# Control_Board.net
KiCad netlist of a schematic drawn in EAGLE
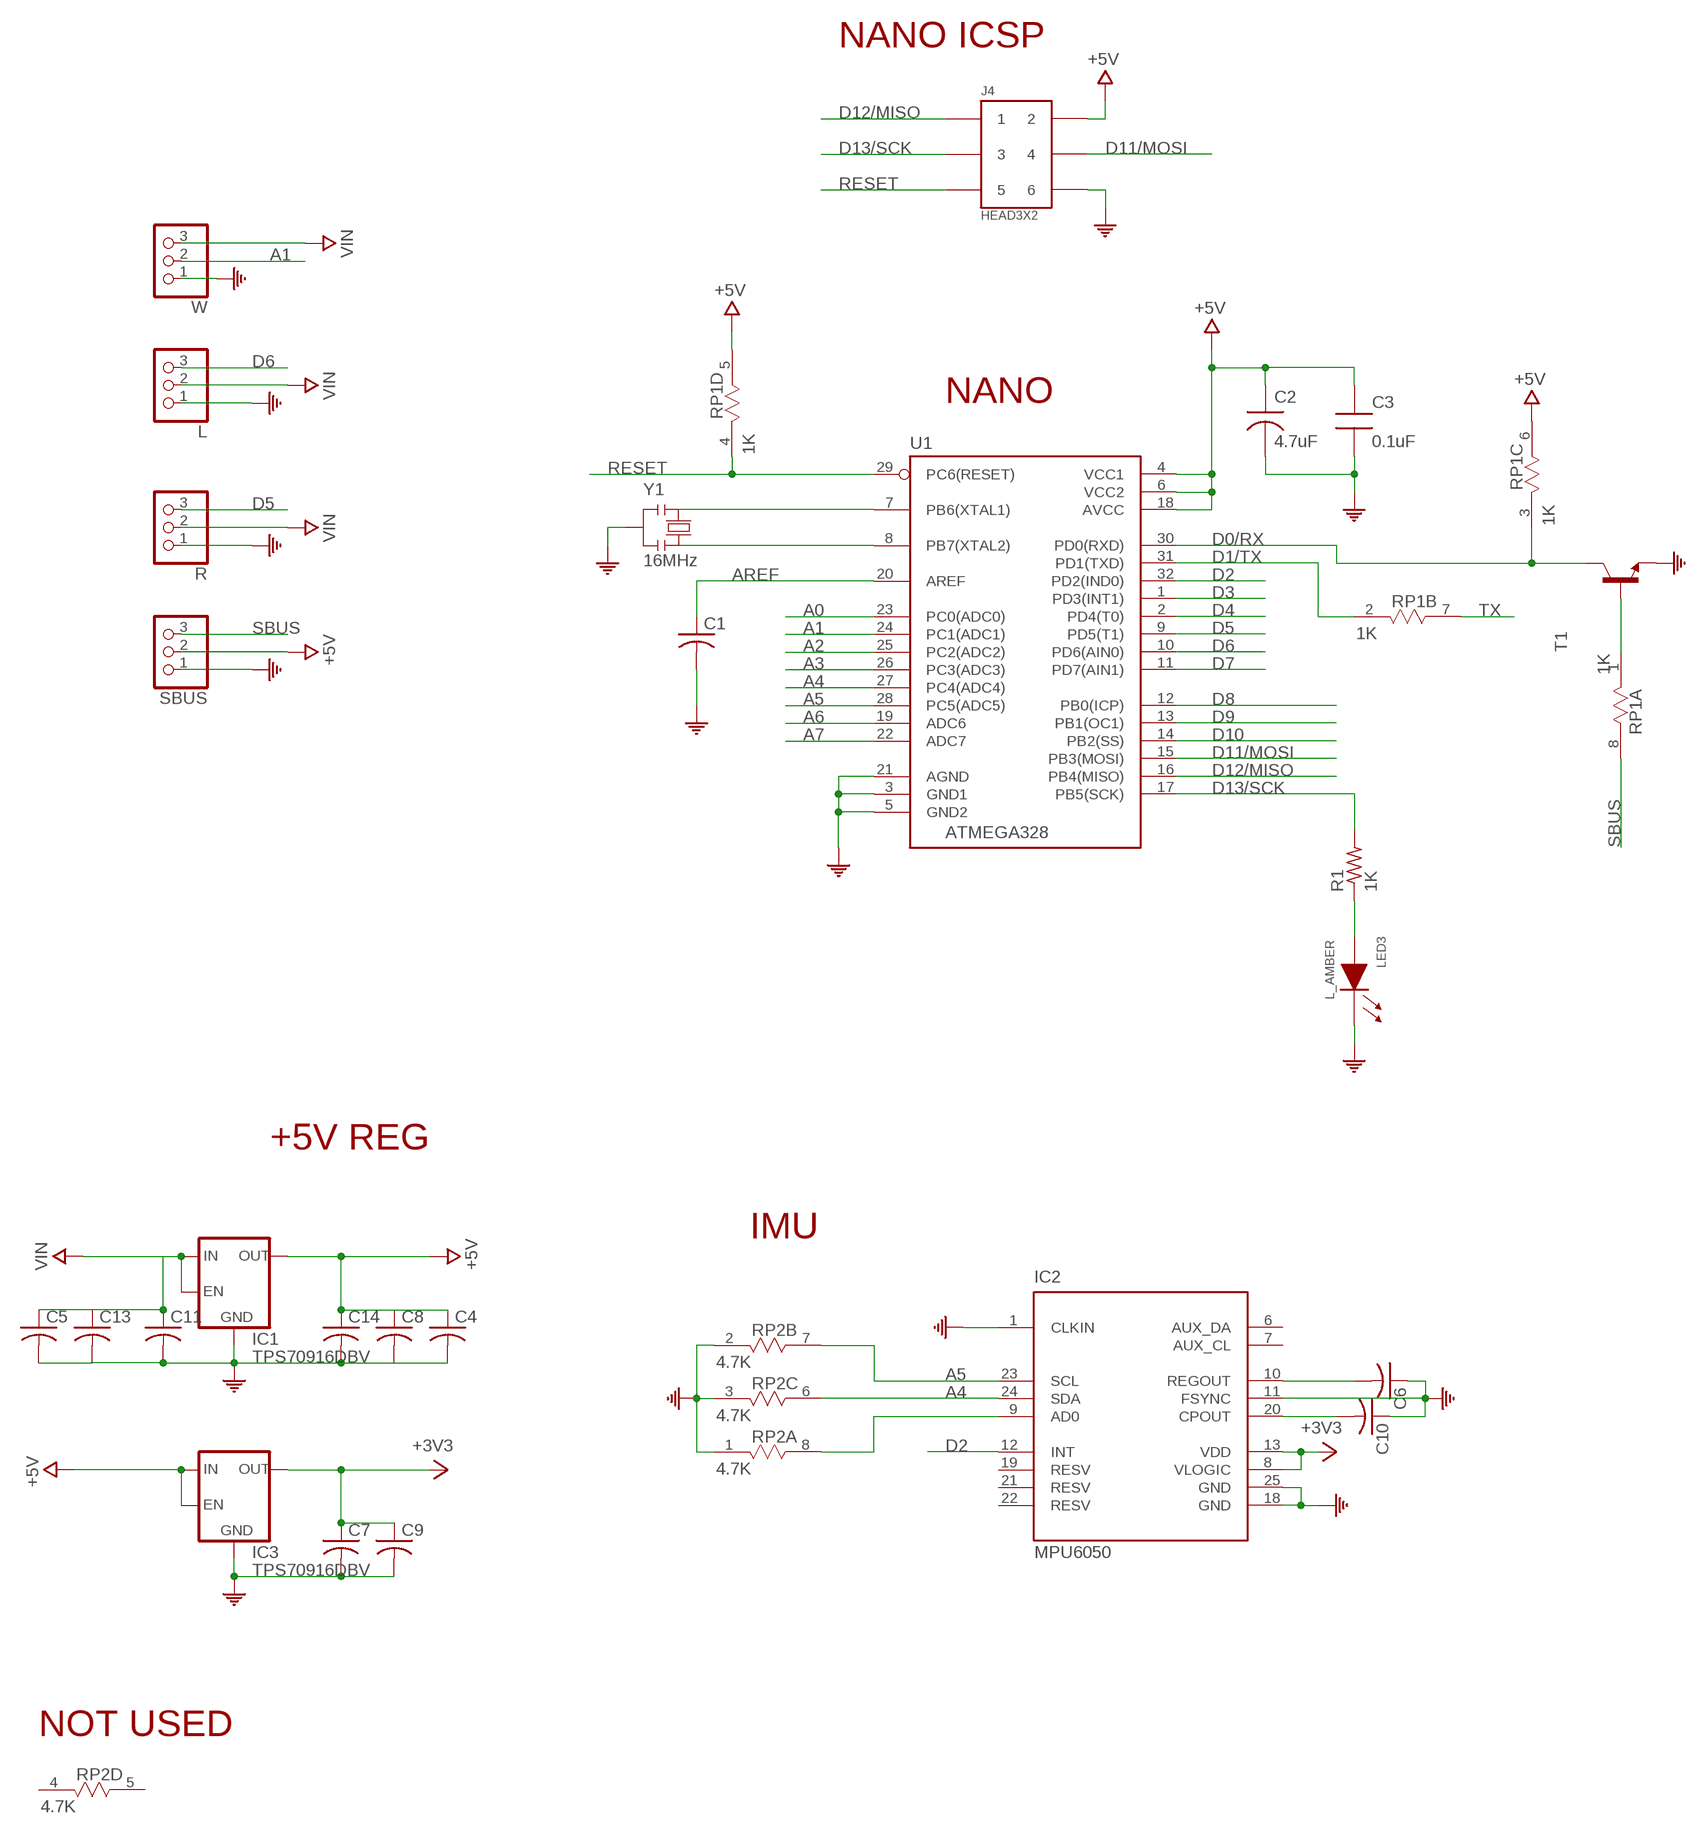
[diagram p0: schematic, sheet 1]

(export (version "E")
  (design (tool "Eeschema 10.0.6"))
  (components
    (comp (ref "C1")
      (value "C-USC0603")
      (footprint "eagle-import:C0603")
      (libsource (lib "eagle-import") (part "C-USC0603"))
    )
    (comp (ref "C2")
      (value "4.7uF")
      (footprint "eagle-import:TAN-A")
      (libsource (lib "eagle-import") (part "CAP-TANA-P"))
    )
    (comp (ref "C3")
      (value "0.1uF")
      (footprint "eagle-import:CAP0805-NP")
      (libsource (lib "eagle-import") (part "CAP0805-NP"))
    )
    (comp (ref "C4")
      (value "C-USC0603")
      (footprint "eagle-import:C0603")
      (libsource (lib "eagle-import") (part "C-USC0603"))
    )
    (comp (ref "C5")
      (value "C-USC0603")
      (footprint "eagle-import:C0603")
      (libsource (lib "eagle-import") (part "C-USC0603"))
    )
    (comp (ref "C6")
      (value "C-USC0603")
      (footprint "eagle-import:C0603")
      (libsource (lib "eagle-import") (part "C-USC0603"))
    )
    (comp (ref "C7")
      (value "C-USC0603")
      (footprint "eagle-import:C0603")
      (libsource (lib "eagle-import") (part "C-USC0603"))
    )
    (comp (ref "C8")
      (value "C-USC0603")
      (footprint "eagle-import:C0603")
      (libsource (lib "eagle-import") (part "C-USC0603"))
    )
    (comp (ref "C9")
      (value "C-USC0603")
      (footprint "eagle-import:C0603")
      (libsource (lib "eagle-import") (part "C-USC0603"))
    )
    (comp (ref "C10")
      (value "C-USC0603")
      (footprint "eagle-import:C0603")
      (libsource (lib "eagle-import") (part "C-USC0603"))
    )
    (comp (ref "C11")
      (value "C-USC0603")
      (footprint "eagle-import:C0603")
      (libsource (lib "eagle-import") (part "C-USC0603"))
    )
    (comp (ref "C13")
      (value "C-USC0603")
      (footprint "eagle-import:C0603")
      (libsource (lib "eagle-import") (part "C-USC0603"))
    )
    (comp (ref "C14")
      (value "C-USC0603")
      (footprint "eagle-import:C0603")
      (libsource (lib "eagle-import") (part "C-USC0603"))
    )
    (comp (ref "IC1")
      (value "TPS70916DBV")
      (footprint "eagle-import:SOT23-5")
      (fields (field (name "MF") "Texas Instruments") (field (name "MPN") "TPS70916DBVT"))
      (libsource (lib "eagle-import") (part "TPS709DBV16"))
    )
    (comp (ref "IC2")
      (value "MPU6050")
      (footprint "eagle-import:QFN50P400X400X95-25T265X275N")
      (libsource (lib "eagle-import") (part "MPU6050"))
    )
    (comp (ref "IC3")
      (value "TPS70916DBV")
      (footprint "eagle-import:SOT23-5")
      (fields (field (name "MF") "Texas Instruments") (field (name "MPN") "TPS70916DBVT"))
      (libsource (lib "eagle-import") (part "TPS709DBV16"))
    )
    (comp (ref "J4")
      (value "HEAD3X2")
      (footprint "eagle-import:HEAD3X2")
      (libsource (lib "eagle-import") (part "HEAD3X2"))
    )
    (comp (ref "L")
      (value "PINHD-1X3")
      (footprint "eagle-import:1X03")
      (libsource (lib "eagle-import") (part "PINHD-1X3"))
    )
    (comp (ref "LED3")
      (value "L_AMBER")
      (footprint "eagle-import:LED0805")
      (libsource (lib "eagle-import") (part "LED0805"))
    )
    (comp (ref "R")
      (value "PINHD-1X3")
      (footprint "eagle-import:1X03")
      (libsource (lib "eagle-import") (part "PINHD-1X3"))
    )
    (comp (ref "R1")
      (value "1K")
      (footprint "eagle-import:R0603")
      (libsource (lib "eagle-import") (part "R-US_R0603"))
    )
    (comp (ref "RP1")
      (value "1K")
      (footprint "eagle-import:RES4NT")
      (libsource (lib "eagle-import") (part "RES4NT"))
    )
    (comp (ref "RP2")
      (value "4.7K")
      (footprint "eagle-import:RES4NT")
      (libsource (lib "eagle-import") (part "RES4NT"))
    )
    (comp (ref "SBUS")
      (value "PINHD-1X3")
      (footprint "eagle-import:1X03")
      (libsource (lib "eagle-import") (part "PINHD-1X3"))
    )
    (comp (ref "T1")
      (value "MMBT3904LT1-NPN-SOT23-BEC")
      (footprint "eagle-import:SOT23-BEC")
      (libsource (lib "eagle-import") (part "-NPN-SOT23-BECMMBT3904LT1"))
    )
    (comp (ref "U1")
      (value "ATMEGA328")
      (footprint "eagle-import:QFP032")
      (libsource (lib "eagle-import") (part "ATMEGA168-20AU"))
    )
    (comp (ref "W")
      (value "PINHD-1X3")
      (footprint "eagle-import:1X03")
      (libsource (lib "eagle-import") (part "PINHD-1X3"))
    )
    (comp (ref "Y1")
      (value "16MHz")
      (footprint "eagle-import:RESONATOR")
      (libsource (lib "eagle-import") (part "RESONATORMU"))
    )
  )
  (nets
    (net (code "1") (name "+3V3") (class "Default")
      (node (ref "C7") (pin "1") (pinfunction "1_1") (pintype "passive"))
      (node (ref "C9") (pin "1") (pinfunction "1_1") (pintype "passive"))
      (node (ref "IC2") (pin "13") (pinfunction "VDD_13") (pintype "power_in"))
      (node (ref "IC2") (pin "8") (pinfunction "VLOGIC_8") (pintype "power_in"))
      (node (ref "IC3") (pin "5") (pinfunction "OUT_5") (pintype "passive"))
    )
    (net (code "2") (name "+5V") (class "Default")
      (node (ref "C14") (pin "1") (pinfunction "1_1") (pintype "passive"))
      (node (ref "C2") (pin "1") (pinfunction "1_1") (pintype "passive"))
      (node (ref "C3") (pin "1") (pinfunction "1_1") (pintype "passive"))
      (node (ref "C4") (pin "1") (pinfunction "1_1") (pintype "passive"))
      (node (ref "C8") (pin "1") (pinfunction "1_1") (pintype "passive"))
      (node (ref "IC1") (pin "5") (pinfunction "OUT_5") (pintype "passive"))
      (node (ref "IC3") (pin "1") (pinfunction "IN_1") (pintype "input"))
      (node (ref "IC3") (pin "3") (pinfunction "EN_3") (pintype "input"))
      (node (ref "J4") (pin "2") (pinfunction "2_2") (pintype "passive"))
      (node (ref "RP1") (pin "5") (pinfunction "2_5") (pintype "passive"))
      (node (ref "RP1") (pin "6") (pinfunction "2_6") (pintype "passive"))
      (node (ref "SBUS") (pin "2") (pinfunction "2_2") (pintype "passive"))
      (node (ref "U1") (pin "18") (pinfunction "AVCC_18") (pintype "passive"))
      (node (ref "U1") (pin "4") (pinfunction "VCC1_4") (pintype "power_in"))
      (node (ref "U1") (pin "6") (pinfunction "VCC2_6") (pintype "power_in"))
    )
    (net (code "3") (name "/A0") (class "Default")
      (node (ref "U1") (pin "23") (pinfunction "PC0(ADC0)_23") (pintype "passive"))
    )
    (net (code "4") (name "/A1") (class "Default")
      (node (ref "U1") (pin "24") (pinfunction "PC1(ADC1)_24") (pintype "passive"))
      (node (ref "W") (pin "2") (pinfunction "2_2") (pintype "passive"))
    )
    (net (code "5") (name "/A2") (class "Default")
      (node (ref "U1") (pin "25") (pinfunction "PC2(ADC2)_25") (pintype "passive"))
    )
    (net (code "6") (name "/A3") (class "Default")
      (node (ref "U1") (pin "26") (pinfunction "PC3(ADC3)_26") (pintype "passive"))
    )
    (net (code "7") (name "/A4") (class "Default")
      (node (ref "IC2") (pin "24") (pinfunction "SDA_24") (pintype "bidirectional"))
      (node (ref "RP2") (pin "6") (pinfunction "2_6") (pintype "passive"))
      (node (ref "U1") (pin "27") (pinfunction "PC4(ADC4)_27") (pintype "passive"))
    )
    (net (code "8") (name "/A5") (class "Default")
      (node (ref "IC2") (pin "23") (pinfunction "SCL_23") (pintype "input"))
      (node (ref "RP2") (pin "7") (pinfunction "2_7") (pintype "passive"))
      (node (ref "U1") (pin "28") (pinfunction "PC5(ADC5)_28") (pintype "passive"))
    )
    (net (code "9") (name "/A6") (class "Default")
      (node (ref "U1") (pin "19") (pinfunction "ADC6_19") (pintype "passive"))
    )
    (net (code "10") (name "/A7") (class "Default")
      (node (ref "U1") (pin "22") (pinfunction "ADC7_22") (pintype "passive"))
    )
    (net (code "11") (name "/AREF") (class "Default")
      (node (ref "C1") (pin "1") (pinfunction "1_1") (pintype "passive"))
      (node (ref "U1") (pin "20") (pinfunction "AREF_20") (pintype "passive"))
    )
    (net (code "12") (name "/D0{slash}RX") (class "Default")
      (node (ref "RP1") (pin "3") (pinfunction "1_3") (pintype "passive"))
      (node (ref "T1") (pin "C") (pinfunction "C_C") (pintype "passive"))
      (node (ref "U1") (pin "30") (pinfunction "PD0(RXD)_30") (pintype "bidirectional"))
    )
    (net (code "13") (name "/D1{slash}TX") (class "Default")
      (node (ref "RP1") (pin "2") (pinfunction "1_2") (pintype "passive"))
      (node (ref "U1") (pin "31") (pinfunction "PD1(TXD)_31") (pintype "bidirectional"))
    )
    (net (code "14") (name "/D2") (class "Default")
      (node (ref "IC2") (pin "12") (pinfunction "INT_12") (pintype "open_collector"))
      (node (ref "U1") (pin "32") (pinfunction "PD2(IND0)_32") (pintype "bidirectional"))
    )
    (net (code "15") (name "/D3") (class "Default")
      (node (ref "U1") (pin "1") (pinfunction "PD3(INT1)_1") (pintype "bidirectional"))
    )
    (net (code "16") (name "/D4") (class "Default")
      (node (ref "U1") (pin "2") (pinfunction "PD4(T0)_2") (pintype "bidirectional"))
    )
    (net (code "17") (name "/D5") (class "Default")
      (node (ref "R") (pin "3") (pinfunction "3_3") (pintype "passive"))
      (node (ref "U1") (pin "9") (pinfunction "PD5(T1)_9") (pintype "bidirectional"))
    )
    (net (code "18") (name "/D6") (class "Default")
      (node (ref "L") (pin "3") (pinfunction "3_3") (pintype "passive"))
      (node (ref "U1") (pin "10") (pinfunction "PD6(AIN0)_10") (pintype "bidirectional"))
    )
    (net (code "19") (name "/D7") (class "Default")
      (node (ref "U1") (pin "11") (pinfunction "PD7(AIN1)_11") (pintype "bidirectional"))
    )
    (net (code "20") (name "/D8") (class "Default")
      (node (ref "U1") (pin "12") (pinfunction "PB0(ICP)_12") (pintype "bidirectional"))
    )
    (net (code "21") (name "/D9") (class "Default")
      (node (ref "U1") (pin "13") (pinfunction "PB1(OC1)_13") (pintype "bidirectional"))
    )
    (net (code "22") (name "/D10") (class "Default")
      (node (ref "U1") (pin "14") (pinfunction "PB2(SS)_14") (pintype "bidirectional"))
    )
    (net (code "23") (name "/D11{slash}MOSI") (class "Default")
      (node (ref "J4") (pin "4") (pinfunction "4_4") (pintype "passive"))
      (node (ref "U1") (pin "15") (pinfunction "PB3(MOSI)_15") (pintype "bidirectional"))
    )
    (net (code "24") (name "/D12{slash}MISO") (class "Default")
      (node (ref "J4") (pin "1") (pinfunction "1_1") (pintype "passive"))
      (node (ref "U1") (pin "16") (pinfunction "PB4(MISO)_16") (pintype "bidirectional"))
    )
    (net (code "25") (name "/D13{slash}SCK") (class "Default")
      (node (ref "J4") (pin "3") (pinfunction "3_3") (pintype "passive"))
      (node (ref "R1") (pin "2") (pinfunction "2_2") (pintype "passive"))
      (node (ref "U1") (pin "17") (pinfunction "PB5(SCK)_17") (pintype "bidirectional"))
    )
    (net (code "26") (name "/RESET") (class "Default")
      (node (ref "J4") (pin "5") (pinfunction "5_5") (pintype "passive"))
      (node (ref "RP1") (pin "4") (pinfunction "1_4") (pintype "passive"))
      (node (ref "U1") (pin "29") (pinfunction "PC6(RESET)_29") (pintype "bidirectional"))
    )
    (net (code "27") (name "/SBUS") (class "Default")
      (node (ref "RP1") (pin "8") (pinfunction "2_8") (pintype "passive"))
      (node (ref "SBUS") (pin "3") (pinfunction "3_3") (pintype "passive"))
    )
    (net (code "28") (name "/TX") (class "Default")
      (node (ref "RP1") (pin "7") (pinfunction "2_7") (pintype "passive"))
    )
    (net (code "29") (name "COM") (class "Default")
      (node (ref "C1") (pin "2") (pinfunction "2_2") (pintype "passive"))
      (node (ref "C10") (pin "1") (pinfunction "1_1") (pintype "passive"))
      (node (ref "C11") (pin "2") (pinfunction "2_2") (pintype "passive"))
      (node (ref "C13") (pin "2") (pinfunction "2_2") (pintype "passive"))
      (node (ref "C14") (pin "2") (pinfunction "2_2") (pintype "passive"))
      (node (ref "C2") (pin "2") (pinfunction "2_2") (pintype "passive"))
      (node (ref "C3") (pin "2") (pinfunction "2_2") (pintype "passive"))
      (node (ref "C4") (pin "2") (pinfunction "2_2") (pintype "passive"))
      (node (ref "C5") (pin "2") (pinfunction "2_2") (pintype "passive"))
      (node (ref "C6") (pin "1") (pinfunction "1_1") (pintype "passive"))
      (node (ref "C7") (pin "2") (pinfunction "2_2") (pintype "passive"))
      (node (ref "C8") (pin "2") (pinfunction "2_2") (pintype "passive"))
      (node (ref "C9") (pin "2") (pinfunction "2_2") (pintype "passive"))
      (node (ref "IC1") (pin "2") (pinfunction "GND_2") (pintype "input"))
      (node (ref "IC2") (pin "1") (pinfunction "CLKIN_1") (pintype "input"))
      (node (ref "IC2") (pin "11") (pinfunction "FSYNC_11") (pintype "input"))
      (node (ref "IC2") (pin "18") (pinfunction "GND_18") (pintype "power_in"))
      (node (ref "IC2") (pin "25") (pinfunction "GND_25") (pintype "power_in"))
      (node (ref "IC3") (pin "2") (pinfunction "GND_2") (pintype "input"))
      (node (ref "J4") (pin "6") (pinfunction "6_6") (pintype "passive"))
      (node (ref "L") (pin "1") (pinfunction "1_1") (pintype "passive"))
      (node (ref "LED3") (pin "1") (pinfunction "CA_1") (pintype "passive"))
      (node (ref "R") (pin "1") (pinfunction "1_1") (pintype "passive"))
      (node (ref "RP2") (pin "1") (pinfunction "1_1") (pintype "passive"))
      (node (ref "RP2") (pin "2") (pinfunction "1_2") (pintype "passive"))
      (node (ref "RP2") (pin "3") (pinfunction "1_3") (pintype "passive"))
      (node (ref "SBUS") (pin "1") (pinfunction "1_1") (pintype "passive"))
      (node (ref "T1") (pin "E") (pinfunction "E_E") (pintype "passive"))
      (node (ref "U1") (pin "21") (pinfunction "AGND_21") (pintype "passive"))
      (node (ref "U1") (pin "3") (pinfunction "GND1_3") (pintype "power_in"))
      (node (ref "U1") (pin "5") (pinfunction "GND2_5") (pintype "power_in"))
      (node (ref "W") (pin "1") (pinfunction "1_1") (pintype "passive"))
      (node (ref "Y1") (pin "2") (pinfunction "2_2") (pintype "passive"))
    )
    (net (code "30") (name "Net-(IC2A-AD0)") (class "Default")
      (node (ref "IC2") (pin "9") (pinfunction "AD0_9") (pintype "input"))
      (node (ref "RP2") (pin "8") (pinfunction "2_8") (pintype "passive"))
    )
    (net (code "31") (name "Net-(IC2A-CPOUT)") (class "Default")
      (node (ref "C10") (pin "2") (pinfunction "2_2") (pintype "passive"))
      (node (ref "IC2") (pin "20") (pinfunction "CPOUT_20") (pintype "output"))
    )
    (net (code "32") (name "Net-(IC2A-REGOUT)") (class "Default")
      (node (ref "C6") (pin "2") (pinfunction "2_2") (pintype "passive"))
      (node (ref "IC2") (pin "10") (pinfunction "REGOUT_10") (pintype "output"))
    )
    (net (code "33") (name "Net-(LED3-AN)") (class "Default")
      (node (ref "LED3") (pin "2") (pinfunction "AN_2") (pintype "passive"))
      (node (ref "R1") (pin "1") (pinfunction "1_1") (pintype "passive"))
    )
    (net (code "34") (name "Net-(RP1-Pad1)") (class "Default")
      (node (ref "RP1") (pin "1") (pinfunction "1_1") (pintype "passive"))
      (node (ref "T1") (pin "B") (pinfunction "B_B") (pintype "passive"))
    )
    (net (code "35") (name "Net-(U1-PB6(XTAL1))") (class "Default")
      (node (ref "U1") (pin "7") (pinfunction "PB6(XTAL1)_7") (pintype "passive"))
      (node (ref "Y1") (pin "1") (pinfunction "1_1") (pintype "passive"))
    )
    (net (code "36") (name "Net-(U1-PB7(XTAL2))") (class "Default")
      (node (ref "U1") (pin "8") (pinfunction "PB7(XTAL2)_8") (pintype "passive"))
      (node (ref "Y1") (pin "3") (pinfunction "3_3") (pintype "passive"))
    )
    (net (code "37") (name "VIN") (class "Default")
      (node (ref "C11") (pin "1") (pinfunction "1_1") (pintype "passive"))
      (node (ref "C13") (pin "1") (pinfunction "1_1") (pintype "passive"))
      (node (ref "C5") (pin "1") (pinfunction "1_1") (pintype "passive"))
      (node (ref "IC1") (pin "1") (pinfunction "IN_1") (pintype "input"))
      (node (ref "IC1") (pin "3") (pinfunction "EN_3") (pintype "input"))
      (node (ref "L") (pin "2") (pinfunction "2_2") (pintype "passive"))
      (node (ref "R") (pin "2") (pinfunction "2_2") (pintype "passive"))
      (node (ref "W") (pin "3") (pinfunction "3_3") (pintype "passive"))
    )
    (net (code "38") (name "unconnected-(IC2A-AUX_CL-Pad7)") (class "Default")
      (node (ref "IC2") (pin "7") (pinfunction "AUX_CL_7") (pintype "bidirectional"))
    )
    (net (code "39") (name "unconnected-(IC2A-AUX_DA-Pad6)") (class "Default")
      (node (ref "IC2") (pin "6") (pinfunction "AUX_DA_6") (pintype "bidirectional"))
    )
    (net (code "40") (name "unconnected-(IC2A-RESV-Pad19)") (class "Default")
      (node (ref "IC2") (pin "19") (pinfunction "RESV_19") (pintype "passive"))
    )
    (net (code "41") (name "unconnected-(IC2A-RESV-Pad21)") (class "Default")
      (node (ref "IC2") (pin "21") (pinfunction "RESV_21") (pintype "passive"))
    )
    (net (code "42") (name "unconnected-(IC2A-RESV-Pad22)") (class "Default")
      (node (ref "IC2") (pin "22") (pinfunction "RESV_22") (pintype "passive"))
    )
    (net (code "43") (name "unconnected-(RP2D-1-Pad4)") (class "Default")
      (node (ref "RP2") (pin "4") (pinfunction "1_4") (pintype "passive"))
    )
    (net (code "44") (name "unconnected-(RP2D-2-Pad5)") (class "Default")
      (node (ref "RP2") (pin "5") (pinfunction "2_5") (pintype "passive"))
    )
  )
)
